# leds_logo.net
KiCad netlist of a schematic drawn in Altium Designer
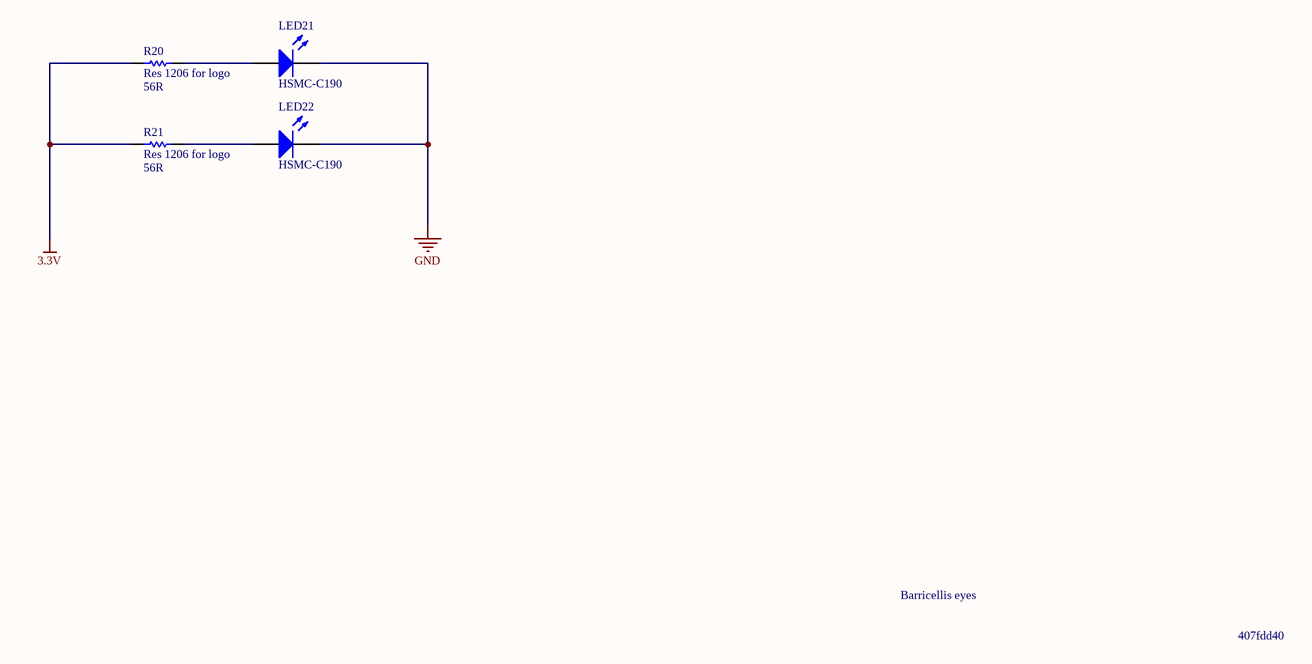
[diagram p0: leds_logo.SchDoc]

(export (version "E")
  (design (tool "Eeschema 10.0.6"))
  (components
    (comp (ref "LED21")
      (value "HSMC-C190")
      (footprint "1.6X0.8X0.8")
      (description "High Performance Chip LED, Red")
      (fields (field (name "PUBLISHER") "Altium Limited"))
      (libsource (lib "Avago Optoelectronic LED") (part "HSMC-C190"))
    )
    (comp (ref "LED22")
      (value "HSMC-C190")
      (footprint "1.6X0.8X0.8")
      (description "High Performance Chip LED, Red")
      (fields (field (name "PUBLISHER") "Altium Limited"))
      (libsource (lib "Avago Optoelectronic LED") (part "HSMC-C190"))
    )
    (comp (ref "R20")
      (value "Res 1206 for logo")
      (footprint "RESC1206(3216)_L")
      (description "56R 0.25W 5% 1206 (3216 Metric)  SMD")
      (fields
        (field (name "TOLERANCE") "5 %")
        (field (name "ALTIUM_VALUE") "56R")
        (field (name "POWER") "0.25 W")
      )
      (libsource (lib "Altium Content Vault") (part "CMP-1014-00056-1"))
    )
    (comp (ref "R21")
      (value "Res 1206 for logo")
      (footprint "RESC1206(3216)_L")
      (description "56R 0.25W 5% 1206 (3216 Metric)  SMD")
      (fields
        (field (name "TOLERANCE") "5 %")
        (field (name "ALTIUM_VALUE") "56R")
        (field (name "POWER") "0.25 W")
      )
      (libsource (lib "Altium Content Vault") (part "CMP-1014-00056-1"))
    )
  )
  (nets
    (net (code "1") (name "3.3V") (class "Default")
      (node (ref "R20") (pin "1") (pinfunction "1_1") (pintype "passive"))
      (node (ref "R21") (pin "1") (pinfunction "1_1") (pintype "passive"))
    )
    (net (code "2") (name "GND") (class "Default")
      (node (ref "LED21") (pin "2") (pinfunction "K_2") (pintype "passive"))
      (node (ref "LED22") (pin "2") (pinfunction "K_2") (pintype "passive"))
    )
    (net (code "3") (name "Net-(LED21-A)") (class "Default")
      (node (ref "LED21") (pin "1") (pinfunction "A_1") (pintype "passive"))
      (node (ref "R20") (pin "2") (pinfunction "2_2") (pintype "passive"))
    )
    (net (code "4") (name "Net-(LED22-A)") (class "Default")
      (node (ref "LED22") (pin "1") (pinfunction "A_1") (pintype "passive"))
      (node (ref "R21") (pin "2") (pinfunction "2_2") (pintype "passive"))
    )
  )
)
